# LED_MATRIX.net
KiCad netlist of a schematic drawn in EAGLE
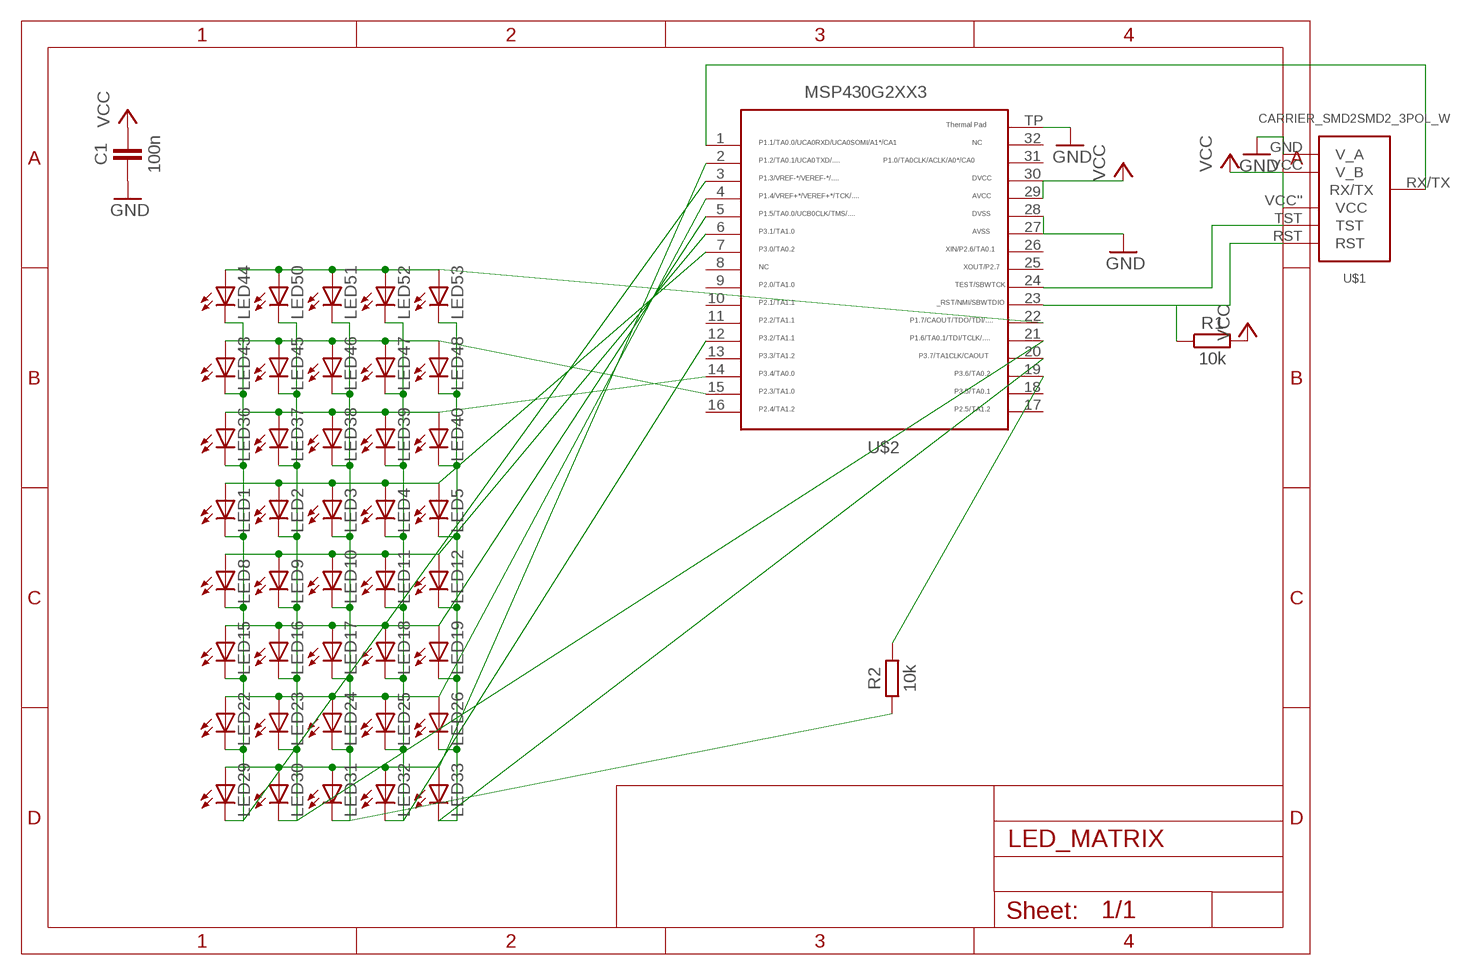
[diagram p0: schematic, sheet 1]

(export (version "E")
  (design (tool "Eeschema 10.0.6"))
  (components
    (comp (ref "C1")
      (value "100n")
      (footprint "eagle-import:603")
      (libsource (lib "eagle-import") (part "CAPACITOR"))
    )
    (comp (ref "LED1")
      (value "LEDCHIPLED_0603")
      (footprint "eagle-import:CHIPLED_0603")
      (libsource (lib "eagle-import") (part "LEDCHIPLED_0603"))
    )
    (comp (ref "LED2")
      (value "LEDCHIPLED_0603")
      (footprint "eagle-import:CHIPLED_0603")
      (libsource (lib "eagle-import") (part "LEDCHIPLED_0603"))
    )
    (comp (ref "LED3")
      (value "LEDCHIPLED_0603")
      (footprint "eagle-import:CHIPLED_0603")
      (libsource (lib "eagle-import") (part "LEDCHIPLED_0603"))
    )
    (comp (ref "LED4")
      (value "LEDCHIPLED_0603")
      (footprint "eagle-import:CHIPLED_0603")
      (libsource (lib "eagle-import") (part "LEDCHIPLED_0603"))
    )
    (comp (ref "LED5")
      (value "LEDCHIPLED_0603")
      (footprint "eagle-import:CHIPLED_0603")
      (libsource (lib "eagle-import") (part "LEDCHIPLED_0603"))
    )
    (comp (ref "LED8")
      (value "LEDCHIPLED_0603")
      (footprint "eagle-import:CHIPLED_0603")
      (libsource (lib "eagle-import") (part "LEDCHIPLED_0603"))
    )
    (comp (ref "LED9")
      (value "LEDCHIPLED_0603")
      (footprint "eagle-import:CHIPLED_0603")
      (libsource (lib "eagle-import") (part "LEDCHIPLED_0603"))
    )
    (comp (ref "LED10")
      (value "LEDCHIPLED_0603")
      (footprint "eagle-import:CHIPLED_0603")
      (libsource (lib "eagle-import") (part "LEDCHIPLED_0603"))
    )
    (comp (ref "LED11")
      (value "LEDCHIPLED_0603")
      (footprint "eagle-import:CHIPLED_0603")
      (libsource (lib "eagle-import") (part "LEDCHIPLED_0603"))
    )
    (comp (ref "LED12")
      (value "LEDCHIPLED_0603")
      (footprint "eagle-import:CHIPLED_0603")
      (libsource (lib "eagle-import") (part "LEDCHIPLED_0603"))
    )
    (comp (ref "LED15")
      (value "LEDCHIPLED_0603")
      (footprint "eagle-import:CHIPLED_0603")
      (libsource (lib "eagle-import") (part "LEDCHIPLED_0603"))
    )
    (comp (ref "LED16")
      (value "LEDCHIPLED_0603")
      (footprint "eagle-import:CHIPLED_0603")
      (libsource (lib "eagle-import") (part "LEDCHIPLED_0603"))
    )
    (comp (ref "LED17")
      (value "LEDCHIPLED_0603")
      (footprint "eagle-import:CHIPLED_0603")
      (libsource (lib "eagle-import") (part "LEDCHIPLED_0603"))
    )
    (comp (ref "LED18")
      (value "LEDCHIPLED_0603")
      (footprint "eagle-import:CHIPLED_0603")
      (libsource (lib "eagle-import") (part "LEDCHIPLED_0603"))
    )
    (comp (ref "LED19")
      (value "LEDCHIPLED_0603")
      (footprint "eagle-import:CHIPLED_0603")
      (libsource (lib "eagle-import") (part "LEDCHIPLED_0603"))
    )
    (comp (ref "LED22")
      (value "LEDCHIPLED_0603")
      (footprint "eagle-import:CHIPLED_0603")
      (libsource (lib "eagle-import") (part "LEDCHIPLED_0603"))
    )
    (comp (ref "LED23")
      (value "LEDCHIPLED_0603")
      (footprint "eagle-import:CHIPLED_0603")
      (libsource (lib "eagle-import") (part "LEDCHIPLED_0603"))
    )
    (comp (ref "LED24")
      (value "LEDCHIPLED_0603")
      (footprint "eagle-import:CHIPLED_0603")
      (libsource (lib "eagle-import") (part "LEDCHIPLED_0603"))
    )
    (comp (ref "LED25")
      (value "LEDCHIPLED_0603")
      (footprint "eagle-import:CHIPLED_0603")
      (libsource (lib "eagle-import") (part "LEDCHIPLED_0603"))
    )
    (comp (ref "LED26")
      (value "LEDCHIPLED_0603")
      (footprint "eagle-import:CHIPLED_0603")
      (libsource (lib "eagle-import") (part "LEDCHIPLED_0603"))
    )
    (comp (ref "LED29")
      (value "LEDCHIPLED_0603")
      (footprint "eagle-import:CHIPLED_0603")
      (libsource (lib "eagle-import") (part "LEDCHIPLED_0603"))
    )
    (comp (ref "LED30")
      (value "LEDCHIPLED_0603")
      (footprint "eagle-import:CHIPLED_0603")
      (libsource (lib "eagle-import") (part "LEDCHIPLED_0603"))
    )
    (comp (ref "LED31")
      (value "LEDCHIPLED_0603")
      (footprint "eagle-import:CHIPLED_0603")
      (libsource (lib "eagle-import") (part "LEDCHIPLED_0603"))
    )
    (comp (ref "LED32")
      (value "LEDCHIPLED_0603")
      (footprint "eagle-import:CHIPLED_0603")
      (libsource (lib "eagle-import") (part "LEDCHIPLED_0603"))
    )
    (comp (ref "LED33")
      (value "LEDCHIPLED_0603")
      (footprint "eagle-import:CHIPLED_0603")
      (libsource (lib "eagle-import") (part "LEDCHIPLED_0603"))
    )
    (comp (ref "LED36")
      (value "LEDCHIPLED_0603")
      (footprint "eagle-import:CHIPLED_0603")
      (libsource (lib "eagle-import") (part "LEDCHIPLED_0603"))
    )
    (comp (ref "LED37")
      (value "LEDCHIPLED_0603")
      (footprint "eagle-import:CHIPLED_0603")
      (libsource (lib "eagle-import") (part "LEDCHIPLED_0603"))
    )
    (comp (ref "LED38")
      (value "LEDCHIPLED_0603")
      (footprint "eagle-import:CHIPLED_0603")
      (libsource (lib "eagle-import") (part "LEDCHIPLED_0603"))
    )
    (comp (ref "LED39")
      (value "LEDCHIPLED_0603")
      (footprint "eagle-import:CHIPLED_0603")
      (libsource (lib "eagle-import") (part "LEDCHIPLED_0603"))
    )
    (comp (ref "LED40")
      (value "LEDCHIPLED_0603")
      (footprint "eagle-import:CHIPLED_0603")
      (libsource (lib "eagle-import") (part "LEDCHIPLED_0603"))
    )
    (comp (ref "LED43")
      (value "LEDCHIPLED_0603")
      (footprint "eagle-import:CHIPLED_0603")
      (libsource (lib "eagle-import") (part "LEDCHIPLED_0603"))
    )
    (comp (ref "LED44")
      (value "LEDCHIPLED_0603")
      (footprint "eagle-import:CHIPLED_0603")
      (libsource (lib "eagle-import") (part "LEDCHIPLED_0603"))
    )
    (comp (ref "LED45")
      (value "LEDCHIPLED_0603")
      (footprint "eagle-import:CHIPLED_0603")
      (libsource (lib "eagle-import") (part "LEDCHIPLED_0603"))
    )
    (comp (ref "LED46")
      (value "LEDCHIPLED_0603")
      (footprint "eagle-import:CHIPLED_0603")
      (libsource (lib "eagle-import") (part "LEDCHIPLED_0603"))
    )
    (comp (ref "LED47")
      (value "LEDCHIPLED_0603")
      (footprint "eagle-import:CHIPLED_0603")
      (libsource (lib "eagle-import") (part "LEDCHIPLED_0603"))
    )
    (comp (ref "LED48")
      (value "LEDCHIPLED_0603")
      (footprint "eagle-import:CHIPLED_0603")
      (libsource (lib "eagle-import") (part "LEDCHIPLED_0603"))
    )
    (comp (ref "LED50")
      (value "LEDCHIPLED_0603")
      (footprint "eagle-import:CHIPLED_0603")
      (libsource (lib "eagle-import") (part "LEDCHIPLED_0603"))
    )
    (comp (ref "LED51")
      (value "LEDCHIPLED_0603")
      (footprint "eagle-import:CHIPLED_0603")
      (libsource (lib "eagle-import") (part "LEDCHIPLED_0603"))
    )
    (comp (ref "LED52")
      (value "LEDCHIPLED_0603")
      (footprint "eagle-import:CHIPLED_0603")
      (libsource (lib "eagle-import") (part "LEDCHIPLED_0603"))
    )
    (comp (ref "LED53")
      (value "LEDCHIPLED_0603")
      (footprint "eagle-import:CHIPLED_0603")
      (libsource (lib "eagle-import") (part "LEDCHIPLED_0603"))
    )
    (comp (ref "R1")
      (value "10k")
      (footprint "eagle-import:603")
      (libsource (lib "eagle-import") (part "RESISTOR0603"))
    )
    (comp (ref "R2")
      (value "10k")
      (footprint "eagle-import:603_SMALL")
      (libsource (lib "eagle-import") (part "RESISTOR0603S"))
    )
    (comp (ref "U$1")
      (value "CARRIER_SMD2SMD2_3POL_W")
      (footprint "eagle-import:CARRIER_SMD2_WIDE_3POL")
      (libsource (lib "eagle-import") (part "CARRIER_SMD2SMD2_3POL_W"))
    )
    (comp (ref "U$2")
      (value "MSP430G2553")
      (footprint "eagle-import:QFN32")
      (libsource (lib "eagle-import") (part "MSP430G2553"))
    )
  )
  (nets
    (net (code "1") (name "GND") (class "Default")
      (node (ref "C1") (pin "1") (pinfunction "1_1") (pintype "passive"))
      (node (ref "U$1") (pin "GND") (pinfunction "V_A_GND") (pintype "bidirectional"))
      (node (ref "U$2") (pin "27") (pinfunction "27_27") (pintype "bidirectional"))
      (node (ref "U$2") (pin "28") (pinfunction "28_28") (pintype "bidirectional"))
      (node (ref "U$2") (pin "TP") (pinfunction "TP_TP") (pintype "bidirectional"))
    )
    (net (code "2") (name "Net-(LED1-PadA)") (class "Default")
      (node (ref "LED1") (pin "A") (pinfunction "A_A") (pintype "passive"))
      (node (ref "LED2") (pin "A") (pinfunction "A_A") (pintype "passive"))
      (node (ref "LED3") (pin "A") (pinfunction "A_A") (pintype "passive"))
      (node (ref "LED4") (pin "A") (pinfunction "A_A") (pintype "passive"))
      (node (ref "LED5") (pin "A") (pinfunction "A_A") (pintype "passive"))
      (node (ref "U$2") (pin "7") (pinfunction "7_7") (pintype "bidirectional"))
    )
    (net (code "3") (name "Net-(LED1-PadC)") (class "Default")
      (node (ref "LED1") (pin "C") (pinfunction "C_C") (pintype "passive"))
      (node (ref "LED15") (pin "C") (pinfunction "C_C") (pintype "passive"))
      (node (ref "LED22") (pin "C") (pinfunction "C_C") (pintype "passive"))
      (node (ref "LED29") (pin "C") (pinfunction "C_C") (pintype "passive"))
      (node (ref "LED36") (pin "C") (pinfunction "C_C") (pintype "passive"))
      (node (ref "LED43") (pin "C") (pinfunction "C_C") (pintype "passive"))
      (node (ref "LED44") (pin "C") (pinfunction "C_C") (pintype "passive"))
      (node (ref "LED8") (pin "C") (pinfunction "C_C") (pintype "passive"))
      (node (ref "U$2") (pin "3") (pinfunction "3_3") (pintype "bidirectional"))
    )
    (net (code "4") (name "Net-(LED10-PadA)") (class "Default")
      (node (ref "LED10") (pin "A") (pinfunction "A_A") (pintype "passive"))
      (node (ref "LED11") (pin "A") (pinfunction "A_A") (pintype "passive"))
      (node (ref "LED12") (pin "A") (pinfunction "A_A") (pintype "passive"))
      (node (ref "LED8") (pin "A") (pinfunction "A_A") (pintype "passive"))
      (node (ref "LED9") (pin "A") (pinfunction "A_A") (pintype "passive"))
      (node (ref "U$2") (pin "6") (pinfunction "6_6") (pintype "bidirectional"))
    )
    (net (code "5") (name "Net-(LED10-PadC)") (class "Default")
      (node (ref "LED10") (pin "C") (pinfunction "C_C") (pintype "passive"))
      (node (ref "LED17") (pin "C") (pinfunction "C_C") (pintype "passive"))
      (node (ref "LED24") (pin "C") (pinfunction "C_C") (pintype "passive"))
      (node (ref "LED3") (pin "C") (pinfunction "C_C") (pintype "passive"))
      (node (ref "LED31") (pin "C") (pinfunction "C_C") (pintype "passive"))
      (node (ref "LED38") (pin "C") (pinfunction "C_C") (pintype "passive"))
      (node (ref "LED46") (pin "C") (pinfunction "C_C") (pintype "passive"))
      (node (ref "LED51") (pin "C") (pinfunction "C_C") (pintype "passive"))
      (node (ref "R2") (pin "1") (pinfunction "1_1") (pintype "passive"))
    )
    (net (code "6") (name "Net-(LED11-PadC)") (class "Default")
      (node (ref "LED11") (pin "C") (pinfunction "C_C") (pintype "passive"))
      (node (ref "LED18") (pin "C") (pinfunction "C_C") (pintype "passive"))
      (node (ref "LED25") (pin "C") (pinfunction "C_C") (pintype "passive"))
      (node (ref "LED32") (pin "C") (pinfunction "C_C") (pintype "passive"))
      (node (ref "LED39") (pin "C") (pinfunction "C_C") (pintype "passive"))
      (node (ref "LED4") (pin "C") (pinfunction "C_C") (pintype "passive"))
      (node (ref "LED47") (pin "C") (pinfunction "C_C") (pintype "passive"))
      (node (ref "LED52") (pin "C") (pinfunction "C_C") (pintype "passive"))
      (node (ref "U$2") (pin "12") (pinfunction "12_12") (pintype "bidirectional"))
    )
    (net (code "7") (name "Net-(LED12-PadC)") (class "Default")
      (node (ref "LED12") (pin "C") (pinfunction "C_C") (pintype "passive"))
      (node (ref "LED19") (pin "C") (pinfunction "C_C") (pintype "passive"))
      (node (ref "LED26") (pin "C") (pinfunction "C_C") (pintype "passive"))
      (node (ref "LED33") (pin "C") (pinfunction "C_C") (pintype "passive"))
      (node (ref "LED40") (pin "C") (pinfunction "C_C") (pintype "passive"))
      (node (ref "LED48") (pin "C") (pinfunction "C_C") (pintype "passive"))
      (node (ref "LED5") (pin "C") (pinfunction "C_C") (pintype "passive"))
      (node (ref "LED53") (pin "C") (pinfunction "C_C") (pintype "passive"))
      (node (ref "U$2") (pin "20") (pinfunction "20_20") (pintype "bidirectional"))
    )
    (net (code "8") (name "Net-(LED15-PadA)") (class "Default")
      (node (ref "LED15") (pin "A") (pinfunction "A_A") (pintype "passive"))
      (node (ref "LED16") (pin "A") (pinfunction "A_A") (pintype "passive"))
      (node (ref "LED17") (pin "A") (pinfunction "A_A") (pintype "passive"))
      (node (ref "LED18") (pin "A") (pinfunction "A_A") (pintype "passive"))
      (node (ref "LED19") (pin "A") (pinfunction "A_A") (pintype "passive"))
      (node (ref "U$2") (pin "5") (pinfunction "5_5") (pintype "bidirectional"))
    )
    (net (code "9") (name "Net-(LED16-PadC)") (class "Default")
      (node (ref "LED16") (pin "C") (pinfunction "C_C") (pintype "passive"))
      (node (ref "LED2") (pin "C") (pinfunction "C_C") (pintype "passive"))
      (node (ref "LED23") (pin "C") (pinfunction "C_C") (pintype "passive"))
      (node (ref "LED30") (pin "C") (pinfunction "C_C") (pintype "passive"))
      (node (ref "LED37") (pin "C") (pinfunction "C_C") (pintype "passive"))
      (node (ref "LED45") (pin "C") (pinfunction "C_C") (pintype "passive"))
      (node (ref "LED50") (pin "C") (pinfunction "C_C") (pintype "passive"))
      (node (ref "LED9") (pin "C") (pinfunction "C_C") (pintype "passive"))
      (node (ref "U$2") (pin "21") (pinfunction "21_21") (pintype "bidirectional"))
    )
    (net (code "10") (name "Net-(LED22-PadA)") (class "Default")
      (node (ref "LED22") (pin "A") (pinfunction "A_A") (pintype "passive"))
      (node (ref "LED23") (pin "A") (pinfunction "A_A") (pintype "passive"))
      (node (ref "LED24") (pin "A") (pinfunction "A_A") (pintype "passive"))
      (node (ref "LED25") (pin "A") (pinfunction "A_A") (pintype "passive"))
      (node (ref "LED26") (pin "A") (pinfunction "A_A") (pintype "passive"))
      (node (ref "U$2") (pin "4") (pinfunction "4_4") (pintype "bidirectional"))
    )
    (net (code "11") (name "Net-(LED29-PadA)") (class "Default")
      (node (ref "LED29") (pin "A") (pinfunction "A_A") (pintype "passive"))
      (node (ref "LED30") (pin "A") (pinfunction "A_A") (pintype "passive"))
      (node (ref "LED31") (pin "A") (pinfunction "A_A") (pintype "passive"))
      (node (ref "LED32") (pin "A") (pinfunction "A_A") (pintype "passive"))
      (node (ref "LED33") (pin "A") (pinfunction "A_A") (pintype "passive"))
      (node (ref "U$2") (pin "2") (pinfunction "2_2") (pintype "bidirectional"))
    )
    (net (code "12") (name "Net-(LED36-PadA)") (class "Default")
      (node (ref "LED36") (pin "A") (pinfunction "A_A") (pintype "passive"))
      (node (ref "LED37") (pin "A") (pinfunction "A_A") (pintype "passive"))
      (node (ref "LED38") (pin "A") (pinfunction "A_A") (pintype "passive"))
      (node (ref "LED39") (pin "A") (pinfunction "A_A") (pintype "passive"))
      (node (ref "LED40") (pin "A") (pinfunction "A_A") (pintype "passive"))
      (node (ref "U$2") (pin "14") (pinfunction "14_14") (pintype "bidirectional"))
    )
    (net (code "13") (name "Net-(LED43-PadA)") (class "Default")
      (node (ref "LED43") (pin "A") (pinfunction "A_A") (pintype "passive"))
      (node (ref "LED45") (pin "A") (pinfunction "A_A") (pintype "passive"))
      (node (ref "LED46") (pin "A") (pinfunction "A_A") (pintype "passive"))
      (node (ref "LED47") (pin "A") (pinfunction "A_A") (pintype "passive"))
      (node (ref "LED48") (pin "A") (pinfunction "A_A") (pintype "passive"))
      (node (ref "U$2") (pin "15") (pinfunction "15_15") (pintype "bidirectional"))
    )
    (net (code "14") (name "Net-(LED44-PadA)") (class "Default")
      (node (ref "LED44") (pin "A") (pinfunction "A_A") (pintype "passive"))
      (node (ref "LED50") (pin "A") (pinfunction "A_A") (pintype "passive"))
      (node (ref "LED51") (pin "A") (pinfunction "A_A") (pintype "passive"))
      (node (ref "LED52") (pin "A") (pinfunction "A_A") (pintype "passive"))
      (node (ref "LED53") (pin "A") (pinfunction "A_A") (pintype "passive"))
      (node (ref "U$2") (pin "22") (pinfunction "22_22") (pintype "bidirectional"))
    )
    (net (code "15") (name "Net-(R1-Pad1)") (class "Default")
      (node (ref "R1") (pin "1") (pinfunction "1_1") (pintype "passive"))
      (node (ref "U$1") (pin "RST") (pinfunction "RST_RST") (pintype "bidirectional"))
      (node (ref "U$2") (pin "23") (pinfunction "23_23") (pintype "bidirectional"))
    )
    (net (code "16") (name "Net-(R2-Pad2)") (class "Default")
      (node (ref "R2") (pin "2") (pinfunction "2_2") (pintype "passive"))
      (node (ref "U$2") (pin "19") (pinfunction "19_19") (pintype "bidirectional"))
    )
    (net (code "17") (name "Net-(U$1-PadRX{slash}TX)") (class "Default")
      (node (ref "U$1") (pin "RX/TX") (pinfunction "RX/TX_RX/TX") (pintype "bidirectional"))
      (node (ref "U$2") (pin "1") (pinfunction "1_1") (pintype "bidirectional"))
    )
    (net (code "18") (name "Net-(U$1-PadTST)") (class "Default")
      (node (ref "U$1") (pin "TST") (pinfunction "TST_TST") (pintype "bidirectional"))
      (node (ref "U$2") (pin "24") (pinfunction "24_24") (pintype "bidirectional"))
    )
    (net (code "19") (name "VCC") (class "Default")
      (node (ref "C1") (pin "2") (pinfunction "2_2") (pintype "passive"))
      (node (ref "R1") (pin "2") (pinfunction "2_2") (pintype "passive"))
      (node (ref "U$1") (pin "VCC") (pinfunction "V_B_VCC") (pintype "bidirectional"))
      (node (ref "U$1") (pin "VCC''") (pinfunction "VCC_VCC''") (pintype "bidirectional"))
      (node (ref "U$2") (pin "29") (pinfunction "29_29") (pintype "bidirectional"))
      (node (ref "U$2") (pin "30") (pinfunction "30_30") (pintype "bidirectional"))
    )
    (net (code "20") (name "unconnected-(U$2-Pad8)") (class "Default")
      (node (ref "U$2") (pin "8") (pinfunction "8_8") (pintype "bidirectional"))
    )
    (net (code "21") (name "unconnected-(U$2-Pad9)") (class "Default")
      (node (ref "U$2") (pin "9") (pinfunction "9_9") (pintype "bidirectional"))
    )
    (net (code "22") (name "unconnected-(U$2-Pad10)") (class "Default")
      (node (ref "U$2") (pin "10") (pinfunction "10_10") (pintype "bidirectional"))
    )
    (net (code "23") (name "unconnected-(U$2-Pad11)") (class "Default")
      (node (ref "U$2") (pin "11") (pinfunction "11_11") (pintype "bidirectional"))
    )
    (net (code "24") (name "unconnected-(U$2-Pad13)") (class "Default")
      (node (ref "U$2") (pin "13") (pinfunction "13_13") (pintype "bidirectional"))
    )
    (net (code "25") (name "unconnected-(U$2-Pad16)") (class "Default")
      (node (ref "U$2") (pin "16") (pinfunction "16_16") (pintype "bidirectional"))
    )
    (net (code "26") (name "unconnected-(U$2-Pad17)") (class "Default")
      (node (ref "U$2") (pin "17") (pinfunction "17_17") (pintype "bidirectional"))
    )
    (net (code "27") (name "unconnected-(U$2-Pad18)") (class "Default")
      (node (ref "U$2") (pin "18") (pinfunction "18_18") (pintype "bidirectional"))
    )
    (net (code "28") (name "unconnected-(U$2-Pad25)") (class "Default")
      (node (ref "U$2") (pin "25") (pinfunction "25_25") (pintype "bidirectional"))
    )
    (net (code "29") (name "unconnected-(U$2-Pad26)") (class "Default")
      (node (ref "U$2") (pin "26") (pinfunction "26_26") (pintype "bidirectional"))
    )
    (net (code "30") (name "unconnected-(U$2-Pad31)") (class "Default")
      (node (ref "U$2") (pin "31") (pinfunction "31_31") (pintype "bidirectional"))
    )
    (net (code "31") (name "unconnected-(U$2-Pad32)") (class "Default")
      (node (ref "U$2") (pin "32") (pinfunction "32_32") (pintype "bidirectional"))
    )
  )
)
